# BLEduino_Shield-Shield.net
KiCad netlist of a schematic drawn in EAGLE
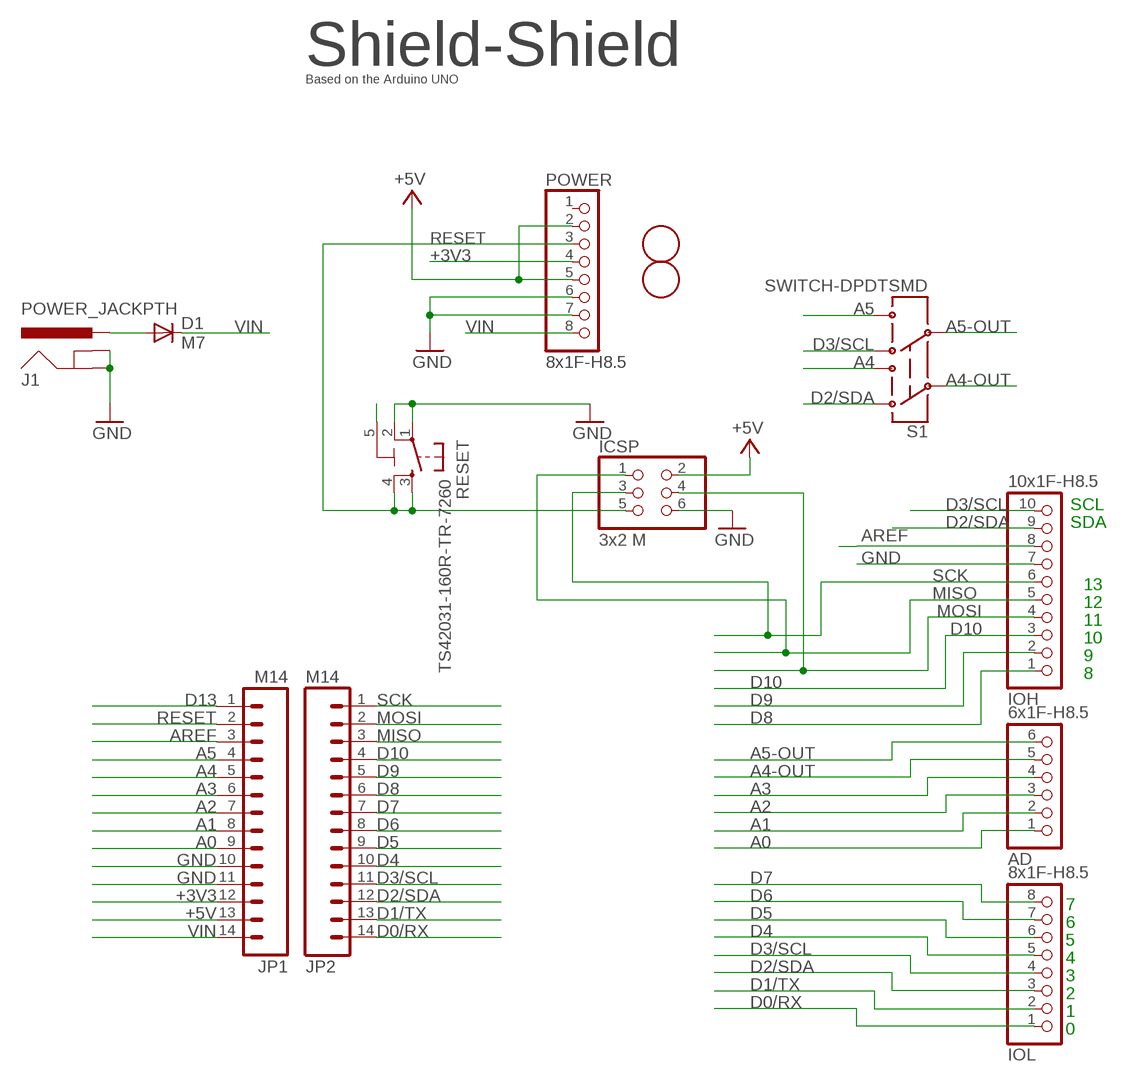
[diagram p0: schematic, sheet 1]

(export (version "E")
  (design (tool "Eeschema 10.0.6"))
  (components
    (comp (ref "AD")
      (value "6x1F-H8.5")
      (footprint "eagle-import:1X06")
      (libsource (lib "eagle-import") (part "PINHD-1X6"))
    )
    (comp (ref "D1")
      (value "M7")
      (footprint "eagle-import:SMB")
      (libsource (lib "eagle-import") (part "DIODE-SMB"))
    )
    (comp (ref "FD1")
      (value "FIDUCIALMOUNT")
      (footprint "eagle-import:FIDUCIA-MOUNT")
      (libsource (lib "eagle-import") (part "FIDUCIALMOUNT"))
    )
    (comp (ref "FD2")
      (value "FIDUCIALMOUNT")
      (footprint "eagle-import:FIDUCIA-MOUNT")
      (libsource (lib "eagle-import") (part "FIDUCIALMOUNT"))
    )
    (comp (ref "ICSP")
      (value "3x2 M")
      (footprint "eagle-import:2X03")
      (libsource (lib "eagle-import") (part "PINHD-2X3"))
    )
    (comp (ref "IOH")
      (value "10x1F-H8.5")
      (footprint "eagle-import:1X10")
      (libsource (lib "eagle-import") (part "PINHD-1X10_ARD"))
    )
    (comp (ref "IOL")
      (value "8x1F-H8.5")
      (footprint "eagle-import:1X08")
      (libsource (lib "eagle-import") (part "PINHD-1X8"))
    )
    (comp (ref "J1")
      (value "POWER_JACKPTH")
      (footprint "eagle-import:POWER_JACK_PTH")
      (libsource (lib "eagle-import") (part "POWER_JACKPTH"))
    )
    (comp (ref "JP1")
      (value "M14")
      (footprint "eagle-import:1X14")
      (libsource (lib "eagle-import") (part "M14"))
    )
    (comp (ref "JP2")
      (value "M14")
      (footprint "eagle-import:1X14")
      (libsource (lib "eagle-import") (part "M14"))
    )
    (comp (ref "POWER")
      (value "8x1F-H8.5")
      (footprint "eagle-import:1X08")
      (libsource (lib "eagle-import") (part "PINHD-1X8"))
    )
    (comp (ref "RESET")
      (value "TS42031-160R-TR-7260")
      (footprint "eagle-import:TS42")
      (libsource (lib "eagle-import") (part "TS42"))
    )
    (comp (ref "S1")
      (value "SWITCH-DPDTSMD")
      (footprint "eagle-import:AYZ0202")
      (libsource (lib "eagle-import") (part "SWITCH-DPDTSMD"))
    )
  )
  (nets
    (net (code "1") (name "+5V") (class "Default")
      (node (ref "ICSP") (pin "2") (pinfunction "2_2") (pintype "passive"))
      (node (ref "JP1") (pin "13") (pinfunction "13_13") (pintype "passive"))
      (node (ref "POWER") (pin "2") (pinfunction "2_2") (pintype "passive"))
      (node (ref "POWER") (pin "5") (pinfunction "5_5") (pintype "passive"))
    )
    (net (code "2") (name "/+3V3") (class "Default")
      (node (ref "JP1") (pin "12") (pinfunction "12_12") (pintype "passive"))
      (node (ref "POWER") (pin "4") (pinfunction "4_4") (pintype "passive"))
    )
    (net (code "3") (name "/A0") (class "Default")
      (node (ref "AD") (pin "1") (pinfunction "1_1") (pintype "passive"))
      (node (ref "JP1") (pin "9") (pinfunction "9_9") (pintype "passive"))
    )
    (net (code "4") (name "/A1") (class "Default")
      (node (ref "AD") (pin "2") (pinfunction "2_2") (pintype "passive"))
      (node (ref "JP1") (pin "8") (pinfunction "8_8") (pintype "passive"))
    )
    (net (code "5") (name "/A2") (class "Default")
      (node (ref "AD") (pin "3") (pinfunction "3_3") (pintype "passive"))
      (node (ref "JP1") (pin "7") (pinfunction "7_7") (pintype "passive"))
    )
    (net (code "6") (name "/A3") (class "Default")
      (node (ref "AD") (pin "4") (pinfunction "4_4") (pintype "passive"))
      (node (ref "JP1") (pin "6") (pinfunction "6_6") (pintype "passive"))
    )
    (net (code "7") (name "/A4") (class "Default")
      (node (ref "JP1") (pin "5") (pinfunction "5_5") (pintype "passive"))
      (node (ref "S1") (pin "3") (pinfunction "3_3") (pintype "bidirectional"))
    )
    (net (code "8") (name "/A4-OUT") (class "Default")
      (node (ref "AD") (pin "5") (pinfunction "5_5") (pintype "passive"))
      (node (ref "S1") (pin "2") (pinfunction "2_2") (pintype "bidirectional"))
    )
    (net (code "9") (name "/A5") (class "Default")
      (node (ref "JP1") (pin "4") (pinfunction "4_4") (pintype "passive"))
      (node (ref "S1") (pin "6") (pinfunction "6_6") (pintype "bidirectional"))
    )
    (net (code "10") (name "/A5-OUT") (class "Default")
      (node (ref "AD") (pin "6") (pinfunction "6_6") (pintype "passive"))
      (node (ref "S1") (pin "5") (pinfunction "5_5") (pintype "bidirectional"))
    )
    (net (code "11") (name "/AREF") (class "Default")
      (node (ref "IOH") (pin "8") (pinfunction "8_8") (pintype "passive"))
      (node (ref "JP1") (pin "3") (pinfunction "3_3") (pintype "passive"))
    )
    (net (code "12") (name "/D0{slash}RX") (class "Default")
      (node (ref "IOL") (pin "1") (pinfunction "1_1") (pintype "passive"))
      (node (ref "JP2") (pin "14") (pinfunction "14_14") (pintype "passive"))
    )
    (net (code "13") (name "/D1{slash}TX") (class "Default")
      (node (ref "IOL") (pin "2") (pinfunction "2_2") (pintype "passive"))
      (node (ref "JP2") (pin "13") (pinfunction "13_13") (pintype "passive"))
    )
    (net (code "14") (name "/D2{slash}SDA") (class "Default")
      (node (ref "IOH") (pin "9") (pinfunction "9_9") (pintype "passive"))
      (node (ref "IOL") (pin "3") (pinfunction "3_3") (pintype "passive"))
      (node (ref "JP2") (pin "12") (pinfunction "12_12") (pintype "passive"))
      (node (ref "S1") (pin "1") (pinfunction "1_1") (pintype "bidirectional"))
    )
    (net (code "15") (name "/D3{slash}SCL") (class "Default")
      (node (ref "IOH") (pin "10") (pinfunction "10_10") (pintype "passive"))
      (node (ref "IOL") (pin "4") (pinfunction "4_4") (pintype "passive"))
      (node (ref "JP2") (pin "11") (pinfunction "11_11") (pintype "passive"))
      (node (ref "S1") (pin "4") (pinfunction "4_4") (pintype "bidirectional"))
    )
    (net (code "16") (name "/D4") (class "Default")
      (node (ref "IOL") (pin "5") (pinfunction "5_5") (pintype "passive"))
      (node (ref "JP2") (pin "10") (pinfunction "10_10") (pintype "passive"))
    )
    (net (code "17") (name "/D5") (class "Default")
      (node (ref "IOL") (pin "6") (pinfunction "6_6") (pintype "passive"))
      (node (ref "JP2") (pin "9") (pinfunction "9_9") (pintype "passive"))
    )
    (net (code "18") (name "/D6") (class "Default")
      (node (ref "IOL") (pin "7") (pinfunction "7_7") (pintype "passive"))
      (node (ref "JP2") (pin "8") (pinfunction "8_8") (pintype "passive"))
    )
    (net (code "19") (name "/D7") (class "Default")
      (node (ref "IOL") (pin "8") (pinfunction "8_8") (pintype "passive"))
      (node (ref "JP2") (pin "7") (pinfunction "7_7") (pintype "passive"))
    )
    (net (code "20") (name "/D8") (class "Default")
      (node (ref "IOH") (pin "1") (pinfunction "1_1") (pintype "passive"))
      (node (ref "JP2") (pin "6") (pinfunction "6_6") (pintype "passive"))
    )
    (net (code "21") (name "/D9") (class "Default")
      (node (ref "IOH") (pin "2") (pinfunction "2_2") (pintype "passive"))
      (node (ref "JP2") (pin "5") (pinfunction "5_5") (pintype "passive"))
    )
    (net (code "22") (name "/D10") (class "Default")
      (node (ref "IOH") (pin "3") (pinfunction "3_3") (pintype "passive"))
      (node (ref "JP2") (pin "4") (pinfunction "4_4") (pintype "passive"))
    )
    (net (code "23") (name "/D13") (class "Default")
      (node (ref "JP1") (pin "1") (pinfunction "1_1") (pintype "passive"))
    )
    (net (code "24") (name "/MISO") (class "Default")
      (node (ref "ICSP") (pin "1") (pinfunction "1_1") (pintype "passive"))
      (node (ref "IOH") (pin "5") (pinfunction "5_5") (pintype "passive"))
      (node (ref "JP2") (pin "3") (pinfunction "3_3") (pintype "passive"))
    )
    (net (code "25") (name "/MOSI") (class "Default")
      (node (ref "ICSP") (pin "4") (pinfunction "4_4") (pintype "passive"))
      (node (ref "IOH") (pin "4") (pinfunction "4_4") (pintype "passive"))
      (node (ref "JP2") (pin "2") (pinfunction "2_2") (pintype "passive"))
    )
    (net (code "26") (name "/RESET") (class "Default")
      (node (ref "ICSP") (pin "5") (pinfunction "5_5") (pintype "passive"))
      (node (ref "JP1") (pin "2") (pinfunction "2_2") (pintype "passive"))
      (node (ref "POWER") (pin "3") (pinfunction "3_3") (pintype "passive"))
      (node (ref "RESET") (pin "3") (pinfunction "3_3") (pintype "passive"))
      (node (ref "RESET") (pin "4") (pinfunction "4_4") (pintype "passive"))
    )
    (net (code "27") (name "/SCK") (class "Default")
      (node (ref "ICSP") (pin "3") (pinfunction "3_3") (pintype "passive"))
      (node (ref "IOH") (pin "6") (pinfunction "6_6") (pintype "passive"))
      (node (ref "JP2") (pin "1") (pinfunction "1_1") (pintype "passive"))
    )
    (net (code "28") (name "/VIN") (class "Default")
      (node (ref "D1") (pin "C") (pinfunction "C_C") (pintype "passive"))
      (node (ref "JP1") (pin "14") (pinfunction "14_14") (pintype "passive"))
      (node (ref "POWER") (pin "8") (pinfunction "8_8") (pintype "passive"))
    )
    (net (code "29") (name "GND") (class "Default")
      (node (ref "ICSP") (pin "6") (pinfunction "6_6") (pintype "passive"))
      (node (ref "IOH") (pin "7") (pinfunction "7_7") (pintype "passive"))
      (node (ref "J1") (pin "GND") (pinfunction "GND_GND") (pintype "bidirectional"))
      (node (ref "J1") (pin "GNDBREAK") (pinfunction "GNDBREAK_GNDBREAK") (pintype "bidirectional"))
      (node (ref "JP1") (pin "10") (pinfunction "10_10") (pintype "passive"))
      (node (ref "JP1") (pin "11") (pinfunction "11_11") (pintype "passive"))
      (node (ref "POWER") (pin "6") (pinfunction "6_6") (pintype "passive"))
      (node (ref "POWER") (pin "7") (pinfunction "7_7") (pintype "passive"))
      (node (ref "RESET") (pin "1") (pinfunction "1_1") (pintype "passive"))
      (node (ref "RESET") (pin "2") (pinfunction "2_2") (pintype "passive"))
    )
    (net (code "30") (name "Net-(D1-PadA)") (class "Default")
      (node (ref "D1") (pin "A") (pinfunction "A_A") (pintype "passive"))
      (node (ref "J1") (pin "PWR") (pinfunction "PWR_PWR") (pintype "bidirectional"))
    )
    (net (code "31") (name "unconnected-(POWER-Pad1)") (class "Default")
      (node (ref "POWER") (pin "1") (pinfunction "1_1") (pintype "passive"))
    )
    (net (code "32") (name "unconnected-(RESET-5-GND-Pad5)") (class "Default")
      (node (ref "RESET") (pin "5") (pinfunction "5-GND_5") (pintype "power_in"))
    )
  )
)
